# DC-DC.net
KiCad netlist of a schematic drawn in Altium Designer
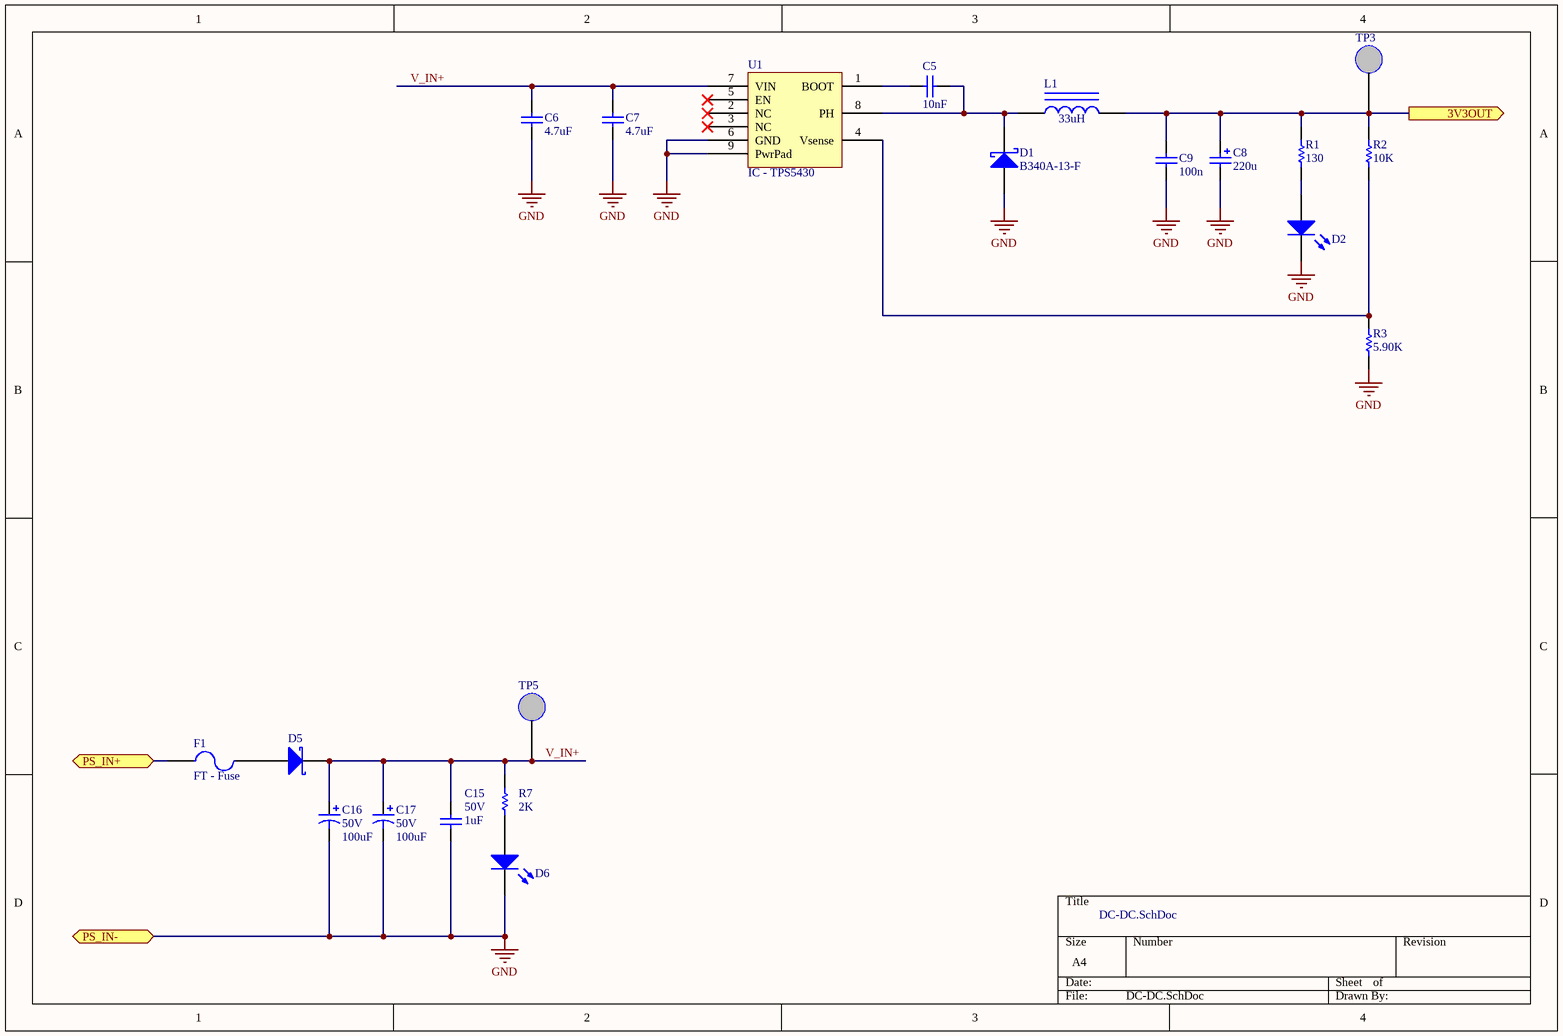
[diagram p0: DC-DC.SchDoc]

(export (version "E")
  (design (tool "Eeschema 10.0.6"))
  (components
    (comp (ref "C5")
      (value "10nF")
      (footprint "CS-0603")
      (description "CAP CER 10000PF 50V 10% X7R 0603")
      (fields (field (name "TOLERANCE") "10%") (field (name "MANUFACTURER") "TDK"))
      (libsource (lib "CHINOOK_LIBRARY") (part "CS - CAPACITOR"))
    )
    (comp (ref "C6")
      (value "4.7uF")
      (footprint "CS-1206")
      (fields
        (field (name "TOLERANCE") "10%")
        (field (name "MANUFACTURER") "Samsung")
        (field (name "VOLTAGE") "16V")
      )
      (libsource (lib "CHINOOK_LIBRARY") (part "CS - CAPACITOR"))
    )
    (comp (ref "C7")
      (value "4.7uF")
      (footprint "CS-1206")
      (fields
        (field (name "TOLERANCE") "10%")
        (field (name "MANUFACTURER") "Samsung")
        (field (name "VOLTAGE") "16V")
      )
      (libsource (lib "CHINOOK_LIBRARY") (part "CS - CAPACITOR"))
    )
    (comp (ref "C8")
      (value "220u")
      (footprint "CS-2312")
      (fields
        (field (name "TOLERANCE") "10%")
        (field (name "VOLTAGE") "VOLTAGE")
        (field (name "Comment") "CS - CAPACITOR POL")
      )
      (libsource (lib "CHINOOK-FOOTPRINT") (part "CS - CAPACITOR POL"))
    )
    (comp (ref "C9")
      (value "100n")
      (footprint "CS-0603")
      (fields
        (field (name "TOLERANCE") "10%")
        (field (name "VOLTAGE") "16V")
        (field (name "Comment") "CS - CAPACITOR")
      )
      (libsource (lib "CHINOOK_LIBRARY") (part "CS - CAPACITOR"))
    )
    (comp (ref "C15")
      (value "1uF")
      (footprint "CS-0603")
      (fields
        (field (name "TOLERANCE") "10%")
        (field (name "VOLTAGE") "50V")
        (field (name "Comment") "CS - CAPACITOR")
      )
      (libsource (lib "CHINOOK_LIBRARY") (part "CS - CAPACITOR"))
    )
    (comp (ref "C16")
      (value "100uF")
      (footprint "CT-CAP-ALUM-8X14")
      (fields
        (field (name "TOLERANCE") "10%")
        (field (name "VOLTAGE") "50V")
        (field (name "Comment") "CT - CAPACITOR ELECTROLYTIC")
      )
      (libsource (lib "CHINOOK_LIBRARY") (part "CT - CAPACITOR ELECTROLYTIC"))
    )
    (comp (ref "C17")
      (value "100uF")
      (footprint "CT-CAP-ALUM-8X14")
      (fields
        (field (name "TOLERANCE") "10%")
        (field (name "VOLTAGE") "50V")
        (field (name "Comment") "CT - CAPACITOR ELECTROLYTIC")
      )
      (libsource (lib "CHINOOK_LIBRARY") (part "CT - CAPACITOR ELECTROLYTIC"))
    )
    (comp (ref "D1")
      (value "B340A-13-F")
      (footprint "DS-DO-214AC-SMA")
      (description "DIODE SCHOTTKY 40V 3A SMA")
      (fields (field (name "MANUFACTURER") "Diodes Incorporated"))
      (libsource (lib "CHINOOK_LIBRARY") (part "DS - Schottky"))
    )
    (comp (ref "D2")
      (value "LED - NORMAL LED")
      (footprint "LED-0603 YELLOW")
      (libsource (lib "CHINOOK_LIBRARY") (part "LED - NORMAL LED"))
    )
    (comp (ref "D5")
      (value "DT - Diode")
      (footprint "TO-220AC")
      (description "Zener Schottky")
      (libsource (lib "Miscellaneous Devices") (part "Diode 18TQ045"))
    )
    (comp (ref "D6")
      (value "LED - NORMAL LED")
      (footprint "LED-0603 YELLOW")
      (libsource (lib "CHINOOK_LIBRARY") (part "LED - NORMAL LED"))
    )
    (comp (ref "F1")
      (value "FT - Fuse")
      (footprint "FT - 5mm x 20mm")
      (fields (field (name "MANUFACTURER") "Schurter Inc"))
      (libsource (lib "CHINOOK_LIBRARY") (part "FT - Fuse"))
    )
    (comp (ref "L1")
      (value "33uH")
      (footprint "LS-Inductor SMD")
      (description "INDUCTOR SHIELD PWR")
      (fields (field (name "MANUFACTURER") "Bourns Inc") (field (name "Comment") "LS - INDUCTOR"))
      (libsource (lib "CHINOOK_LIBRARY") (part "LS - INDUCTOR"))
    )
    (comp (ref "R1")
      (value "130")
      (footprint "RS-0603")
      (fields
        (field (name "TOLERANCE") "RES TOL")
        (field (name "POWER") "RES POWER")
        (field (name "Comment") "RS - RESISTOR")
      )
      (libsource (lib "CHINOOK_LIBRARY") (part "RS - RESISTOR"))
    )
    (comp (ref "R2")
      (value "10K")
      (footprint "RS-0603")
      (fields
        (field (name "TOLERANCE") "RES TOL")
        (field (name "POWER") "RES POWER")
        (field (name "Comment") "RS - RESISTOR")
      )
      (libsource (lib "CHINOOK_LIBRARY") (part "RS - RESISTOR"))
    )
    (comp (ref "R3")
      (value "5.90K")
      (footprint "RS-0603")
      (fields
        (field (name "TOLERANCE") "RES TOL")
        (field (name "POWER") "RES POWER")
        (field (name "Comment") "RS - RESISTOR")
      )
      (libsource (lib "CHINOOK_LIBRARY") (part "RS - RESISTOR"))
    )
    (comp (ref "R7")
      (value "2K")
      (footprint "RS-0603")
      (fields
        (field (name "TOLERANCE") "RES TOL")
        (field (name "POWER") "1/10W")
        (field (name "Comment") "RS - RESISTOR")
      )
      (libsource (lib "CHINOOK_LIBRARY") (part "RS - RESISTOR"))
    )
    (comp (ref "TP3")
      (value "5003K")
      (footprint "TP - VERTICAL")
      (libsource (lib "CHINOOK_LIBRARY") (part "TP - Test point vertical"))
    )
    (comp (ref "TP5")
      (value "5003K")
      (footprint "TP - VERTICAL")
      (libsource (lib "CHINOOK_LIBRARY") (part "TP - Test point vertical"))
    )
    (comp (ref "U1")
      (value "IC - TPS5430")
      (footprint "IC-SOIC8-POWERPAD")
      (description "IC REG BUCK ADJ 3A 8SOPWRPAD")
      (fields (field (name "MANUFACTURER") "Texas Instruments") (field (name "PART NUMBER") "TPS5430"))
      (libsource (lib "CHINOOK_LIBRARY") (part "IC - TPS5430"))
    )
  )
  (nets
    (net (code "1") (name "/3V3OUT") (class "Default")
      (node (ref "C8") (pin "1") (pinfunction "1_1") (pintype "passive"))
      (node (ref "C9") (pin "2") (pinfunction "2_2") (pintype "passive"))
      (node (ref "L1") (pin "2") (pinfunction "2_2") (pintype "passive"))
      (node (ref "R1") (pin "1") (pinfunction "1_1") (pintype "passive"))
      (node (ref "R2") (pin "1") (pinfunction "1_1") (pintype "passive"))
      (node (ref "TP3") (pin "1") (pinfunction "1_1") (pintype "passive"))
    )
    (net (code "2") (name "/PS_IN+") (class "Default")
      (node (ref "F1") (pin "1") (pinfunction "1_1") (pintype "passive"))
    )
    (net (code "3") (name "/V_IN+") (class "Default")
      (node (ref "C15") (pin "2") (pinfunction "2_2") (pintype "passive"))
      (node (ref "C16") (pin "1") (pinfunction "1_1") (pintype "passive"))
      (node (ref "C17") (pin "1") (pinfunction "1_1") (pintype "passive"))
      (node (ref "C6") (pin "2") (pinfunction "2_2") (pintype "passive"))
      (node (ref "C7") (pin "2") (pinfunction "2_2") (pintype "passive"))
      (node (ref "D5") (pin "1") (pinfunction "K_1") (pintype "passive"))
      (node (ref "R7") (pin "2") (pinfunction "2_2") (pintype "passive"))
      (node (ref "TP5") (pin "1") (pinfunction "1_1") (pintype "passive"))
      (node (ref "U1") (pin "7") (pinfunction "VIN_7") (pintype "passive"))
    )
    (net (code "4") (name "GND") (class "Default")
      (node (ref "C15") (pin "1") (pinfunction "1_1") (pintype "passive"))
      (node (ref "C16") (pin "2") (pinfunction "2_2") (pintype "passive"))
      (node (ref "C17") (pin "2") (pinfunction "2_2") (pintype "passive"))
      (node (ref "C6") (pin "1") (pinfunction "1_1") (pintype "passive"))
      (node (ref "C7") (pin "1") (pinfunction "1_1") (pintype "passive"))
      (node (ref "C8") (pin "2") (pinfunction "2_2") (pintype "passive"))
      (node (ref "C9") (pin "1") (pinfunction "1_1") (pintype "passive"))
      (node (ref "D1") (pin "A") (pinfunction "A_A") (pintype "passive"))
      (node (ref "D2") (pin "K") (pinfunction "K_K") (pintype "passive"))
      (node (ref "D6") (pin "K") (pinfunction "K_K") (pintype "passive"))
      (node (ref "R3") (pin "2") (pinfunction "2_2") (pintype "passive"))
      (node (ref "U1") (pin "6") (pinfunction "GND_6") (pintype "passive"))
      (node (ref "U1") (pin "9") (pinfunction "PwrPad_9") (pintype "passive"))
    )
    (net (code "5") (name "Net-(D2-PadA)") (class "Default")
      (node (ref "D2") (pin "A") (pinfunction "A_A") (pintype "passive"))
      (node (ref "R1") (pin "2") (pinfunction "2_2") (pintype "passive"))
    )
    (net (code "6") (name "Net-(D5-A)") (class "Default")
      (node (ref "D5") (pin "3") (pinfunction "A_3") (pintype "passive"))
      (node (ref "F1") (pin "2") (pinfunction "2_2") (pintype "passive"))
    )
    (net (code "7") (name "Net-(D6-PadA)") (class "Default")
      (node (ref "D6") (pin "A") (pinfunction "A_A") (pintype "passive"))
      (node (ref "R7") (pin "1") (pinfunction "1_1") (pintype "passive"))
    )
    (net (code "8") (name "Net-(U1-BOOT)") (class "Default")
      (node (ref "C5") (pin "2") (pinfunction "2_2") (pintype "passive"))
      (node (ref "U1") (pin "1") (pinfunction "BOOT_1") (pintype "passive"))
    )
    (net (code "9") (name "Net-(U1-PH)") (class "Default")
      (node (ref "C5") (pin "1") (pinfunction "1_1") (pintype "passive"))
      (node (ref "D1") (pin "K") (pinfunction "K_K") (pintype "passive"))
      (node (ref "L1") (pin "1") (pinfunction "1_1") (pintype "passive"))
      (node (ref "U1") (pin "8") (pinfunction "PH_8") (pintype "passive"))
    )
    (net (code "10") (name "Net-(U1-Vsense)") (class "Default")
      (node (ref "R2") (pin "2") (pinfunction "2_2") (pintype "passive"))
      (node (ref "R3") (pin "1") (pinfunction "1_1") (pintype "passive"))
      (node (ref "U1") (pin "4") (pinfunction "Vsense_4") (pintype "passive"))
    )
    (net (code "11") (name "unconnected-(U1-EN-Pad5)") (class "Default")
      (node (ref "U1") (pin "5") (pinfunction "EN_5") (pintype "passive+no_connect"))
    )
    (net (code "12") (name "unconnected-(U1-NC-Pad2)") (class "Default")
      (node (ref "U1") (pin "2") (pinfunction "NC_2") (pintype "passive+no_connect"))
    )
    (net (code "13") (name "unconnected-(U1-NC-Pad3)") (class "Default")
      (node (ref "U1") (pin "3") (pinfunction "NC_3") (pintype "passive+no_connect"))
    )
  )
)
